# RGB.net
KiCad netlist of a schematic drawn in Altium Designer
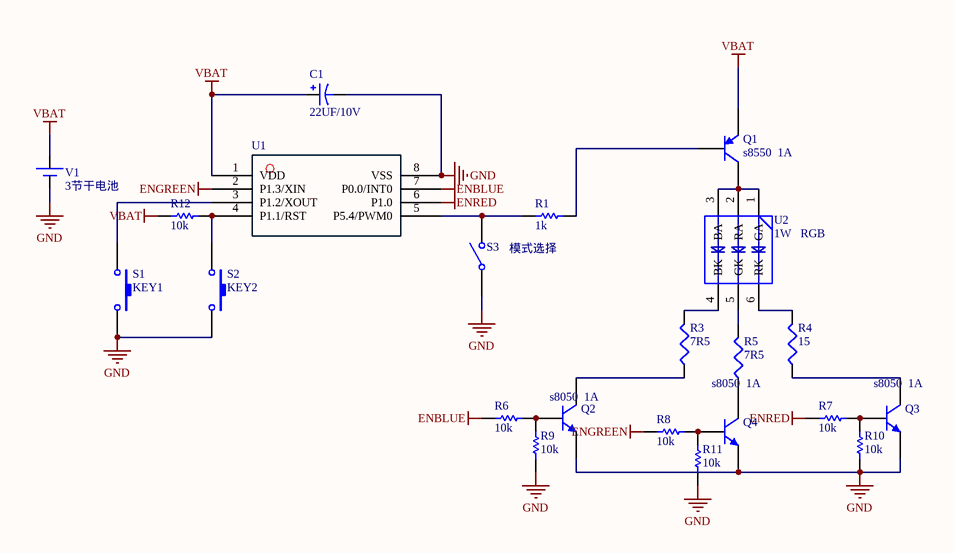
[diagram p0: RGB棒.SchDoc]

(export (version "E")
  (design (tool "Eeschema 10.0.6"))
  (components
    (comp (ref "C1")
      (value "22UF/10V")
      (footprint "R0805-S")
      (description "Polarized Capacitor (Radial)")
      (fields (field (name "PUBLISHER") "Altium Limited"))
      (libsource (lib "Miscellaneous Devices") (part "Cap Pol1"))
    )
    (comp (ref "Q1")
      (value "s8550  1A")
      (footprint "3906_SOT23")
      (description "PNP General Purpose Amplifier")
      (fields (field (name "PUBLISHER") "Altium Limited"))
      (libsource (lib "Schlib1") (part "2N3906"))
    )
    (comp (ref "Q2")
      (value "s8050  1A")
      (footprint "3904_SOT23")
      (description "NPN General Purpose Amplifier")
      (fields (field (name "PUBLISHER") "Altium Limited"))
      (libsource (lib "Miscellaneous Devices") (part "2N3904"))
    )
    (comp (ref "Q3")
      (value "s8050  1A")
      (footprint "3904_SOT23")
      (description "NPN General Purpose Amplifier")
      (fields (field (name "PUBLISHER") "Altium Limited"))
      (libsource (lib "Miscellaneous Devices") (part "2N3904"))
    )
    (comp (ref "Q4")
      (value "s8050  1A")
      (footprint "3904_SOT23")
      (description "NPN General Purpose Amplifier")
      (fields (field (name "PUBLISHER") "Altium Limited"))
      (libsource (lib "Miscellaneous Devices") (part "2N3904"))
    )
    (comp (ref "R1")
      (value "1k")
      (footprint "R0603-s")
      (description "Resistor")
      (fields (field (name "PUBLISHER") "Altium Limited"))
      (libsource (lib "Schlib1") (part "Res1"))
    )
    (comp (ref "R3")
      (value "7R5")
      (footprint "R1206S")
      (description "Resistor")
      (fields (field (name "PUBLISHER") "Altium Limited"))
      (libsource (lib "Schlib1") (part "Res3"))
    )
    (comp (ref "R4")
      (value "15")
      (footprint "R1206S")
      (description "Resistor")
      (fields (field (name "PUBLISHER") "Altium Limited"))
      (libsource (lib "Schlib1") (part "Res3"))
    )
    (comp (ref "R5")
      (value "7R5")
      (footprint "R1206S")
      (description "Resistor")
      (fields (field (name "PUBLISHER") "Altium Limited"))
      (libsource (lib "Schlib1") (part "Res3"))
    )
    (comp (ref "R6")
      (value "10k")
      (footprint "R0603-s")
      (description "Resistor")
      (fields (field (name "PUBLISHER") "Altium Limited"))
      (libsource (lib "Schlib1") (part "Res1"))
    )
    (comp (ref "R7")
      (value "10k")
      (footprint "R0603-s")
      (description "Resistor")
      (fields (field (name "PUBLISHER") "Altium Limited"))
      (libsource (lib "Schlib1") (part "Res1"))
    )
    (comp (ref "R8")
      (value "10k")
      (footprint "R0603-s")
      (description "Resistor")
      (fields (field (name "PUBLISHER") "Altium Limited"))
      (libsource (lib "Schlib1") (part "Res1"))
    )
    (comp (ref "R9")
      (value "10k")
      (footprint "R0603-s")
      (description "Resistor")
      (fields (field (name "PUBLISHER") "Altium Limited"))
      (libsource (lib "Schlib1") (part "Res1"))
    )
    (comp (ref "R10")
      (value "10k")
      (footprint "R0603-s")
      (description "Resistor")
      (fields (field (name "PUBLISHER") "Altium Limited"))
      (libsource (lib "Schlib1") (part "Res1"))
    )
    (comp (ref "R11")
      (value "10k")
      (footprint "R0603-s")
      (description "Resistor")
      (fields (field (name "PUBLISHER") "Altium Limited"))
      (libsource (lib "Schlib1") (part "Res1"))
    )
    (comp (ref "R12")
      (value "10k")
      (footprint "R0603-s")
      (description "Resistor")
      (fields (field (name "PUBLISHER") "Altium Limited"))
      (libsource (lib "Schlib1") (part "Res1"))
    )
    (comp (ref "S1")
      (value "KEY1")
      (footprint "SW-H - duplicate")
      (description "Switch")
      (fields (field (name "PUBLISHER") "Altium Limited"))
      (libsource (lib "*") (part "SW-PB"))
    )
    (comp (ref "S2")
      (value "KEY2")
      (footprint "SW-H - duplicate")
      (description "Switch")
      (fields (field (name "PUBLISHER") "Altium Limited"))
      (libsource (lib "*") (part "SW-PB"))
    )
    (comp (ref "S3")
      (value "SW-SPST")
      (footprint "SPST-2")
      (description "Single-Pole, Single-Throw Switch")
      (fields (field (name "PUBLISHER") "Altium Limited"))
      (libsource (lib "Miscellaneous Devices") (part "SW-SPST"))
    )
    (comp (ref "U1") (value "~") (footprint "SO14") (libsource (lib "Schlib1") (part "sn8p2501-8PIN")))
    (comp (ref "U2") (value "1W   RGB") (footprint "LED5050") (libsource (lib "Schlib1") (part "LED5050")))
    (comp (ref "V1") (value "3节干电池") (footprint "Model Name") (libsource (lib "Schlib1") (part "BAT-LI")))
  )
  (nets
    (net (code "1") (name "ENBLUE") (class "Default")
      (node (ref "R6") (pin "1") (pinfunction "1_1") (pintype "passive"))
      (node (ref "U1") (pin "7") (pinfunction "P0.0/INT0_7") (pintype "passive"))
    )
    (net (code "2") (name "ENGREEN") (class "Default")
      (node (ref "R8") (pin "1") (pinfunction "1_1") (pintype "passive"))
      (node (ref "U1") (pin "2") (pinfunction "P1.3/XIN_2") (pintype "passive"))
    )
    (net (code "3") (name "ENRED") (class "Default")
      (node (ref "R7") (pin "1") (pinfunction "1_1") (pintype "passive"))
      (node (ref "U1") (pin "6") (pinfunction "P1.0_6") (pintype "passive"))
    )
    (net (code "4") (name "GND") (class "Default")
      (node (ref "C1") (pin "2") (pinfunction "2_2") (pintype "passive"))
      (node (ref "Q2") (pin "1") (pinfunction "E_1") (pintype "passive"))
      (node (ref "Q3") (pin "1") (pinfunction "E_1") (pintype "passive"))
      (node (ref "Q4") (pin "1") (pinfunction "E_1") (pintype "passive"))
      (node (ref "R10") (pin "1") (pinfunction "1_1") (pintype "passive"))
      (node (ref "R11") (pin "1") (pinfunction "1_1") (pintype "passive"))
      (node (ref "R9") (pin "1") (pinfunction "1_1") (pintype "passive"))
      (node (ref "S1") (pin "2") (pinfunction "2_2") (pintype "passive"))
      (node (ref "S2") (pin "2") (pinfunction "2_2") (pintype "passive"))
      (node (ref "S3") (pin "1") (pinfunction "COMMON_1") (pintype "passive"))
      (node (ref "U1") (pin "8") (pinfunction "VSS_8") (pintype "passive"))
      (node (ref "V1") (pin "2") (pinfunction "N_2") (pintype "power_in"))
    )
    (net (code "5") (name "Net-(Q1-B)") (class "Default")
      (node (ref "Q1") (pin "2") (pinfunction "B_2") (pintype "passive"))
      (node (ref "R1") (pin "2") (pinfunction "2_2") (pintype "passive"))
    )
    (net (code "6") (name "Net-(Q1-C)") (class "Default")
      (node (ref "Q1") (pin "3") (pinfunction "C_3") (pintype "passive"))
      (node (ref "U2") (pin "1") (pinfunction "GA_1") (pintype "passive"))
      (node (ref "U2") (pin "2") (pinfunction "RA_2") (pintype "passive"))
      (node (ref "U2") (pin "3") (pinfunction "BA_3") (pintype "passive"))
    )
    (net (code "7") (name "Net-(Q2-B)") (class "Default")
      (node (ref "Q2") (pin "2") (pinfunction "B_2") (pintype "passive"))
      (node (ref "R6") (pin "2") (pinfunction "2_2") (pintype "passive"))
      (node (ref "R9") (pin "2") (pinfunction "2_2") (pintype "passive"))
    )
    (net (code "8") (name "Net-(Q2-C)") (class "Default")
      (node (ref "Q2") (pin "3") (pinfunction "C_3") (pintype "passive"))
      (node (ref "R3") (pin "1") (pinfunction "1_1") (pintype "passive"))
    )
    (net (code "9") (name "Net-(Q3-B)") (class "Default")
      (node (ref "Q3") (pin "2") (pinfunction "B_2") (pintype "passive"))
      (node (ref "R10") (pin "2") (pinfunction "2_2") (pintype "passive"))
      (node (ref "R7") (pin "2") (pinfunction "2_2") (pintype "passive"))
    )
    (net (code "10") (name "Net-(Q3-C)") (class "Default")
      (node (ref "Q3") (pin "3") (pinfunction "C_3") (pintype "passive"))
      (node (ref "R4") (pin "1") (pinfunction "1_1") (pintype "passive"))
    )
    (net (code "11") (name "Net-(Q4-B)") (class "Default")
      (node (ref "Q4") (pin "2") (pinfunction "B_2") (pintype "passive"))
      (node (ref "R11") (pin "2") (pinfunction "2_2") (pintype "passive"))
      (node (ref "R8") (pin "2") (pinfunction "2_2") (pintype "passive"))
    )
    (net (code "12") (name "Net-(Q4-C)") (class "Default")
      (node (ref "Q4") (pin "3") (pinfunction "C_3") (pintype "passive"))
      (node (ref "R5") (pin "1") (pinfunction "1_1") (pintype "passive"))
    )
    (net (code "13") (name "Net-(S3-NO)") (class "Default")
      (node (ref "R1") (pin "1") (pinfunction "1_1") (pintype "passive"))
      (node (ref "S3") (pin "2") (pinfunction "NO_2") (pintype "passive"))
      (node (ref "U1") (pin "5") (pinfunction "P5.4/PWM0_5") (pintype "passive"))
    )
    (net (code "14") (name "Net-(U1-P1.1{slash}RST)") (class "Default")
      (node (ref "R12") (pin "1") (pinfunction "1_1") (pintype "passive"))
      (node (ref "S2") (pin "1") (pinfunction "1_1") (pintype "passive"))
      (node (ref "U1") (pin "4") (pinfunction "P1.1/RST_4") (pintype "passive"))
    )
    (net (code "15") (name "Net-(U1-P1.2{slash}XOUT)") (class "Default")
      (node (ref "S1") (pin "1") (pinfunction "1_1") (pintype "passive"))
      (node (ref "U1") (pin "3") (pinfunction "P1.2/XOUT_3") (pintype "passive"))
    )
    (net (code "16") (name "Net-(U2-BK)") (class "Default")
      (node (ref "R3") (pin "2") (pinfunction "2_2") (pintype "passive"))
      (node (ref "U2") (pin "4") (pinfunction "BK_4") (pintype "passive"))
    )
    (net (code "17") (name "Net-(U2-GK)") (class "Default")
      (node (ref "R5") (pin "2") (pinfunction "2_2") (pintype "passive"))
      (node (ref "U2") (pin "5") (pinfunction "GK_5") (pintype "passive"))
    )
    (net (code "18") (name "Net-(U2-RK)") (class "Default")
      (node (ref "R4") (pin "2") (pinfunction "2_2") (pintype "passive"))
      (node (ref "U2") (pin "6") (pinfunction "RK_6") (pintype "passive"))
    )
    (net (code "19") (name "VBAT") (class "Default")
      (node (ref "C1") (pin "1") (pinfunction "1_1") (pintype "passive"))
      (node (ref "Q1") (pin "1") (pinfunction "E_1") (pintype "passive"))
      (node (ref "R12") (pin "2") (pinfunction "2_2") (pintype "passive"))
      (node (ref "U1") (pin "1") (pinfunction "VDD_1") (pintype "passive"))
      (node (ref "V1") (pin "1") (pinfunction "P_1") (pintype "power_in"))
    )
  )
)
